# 03_-_SCHEMATIC.net
KiCad netlist of a schematic drawn in Altium Designer
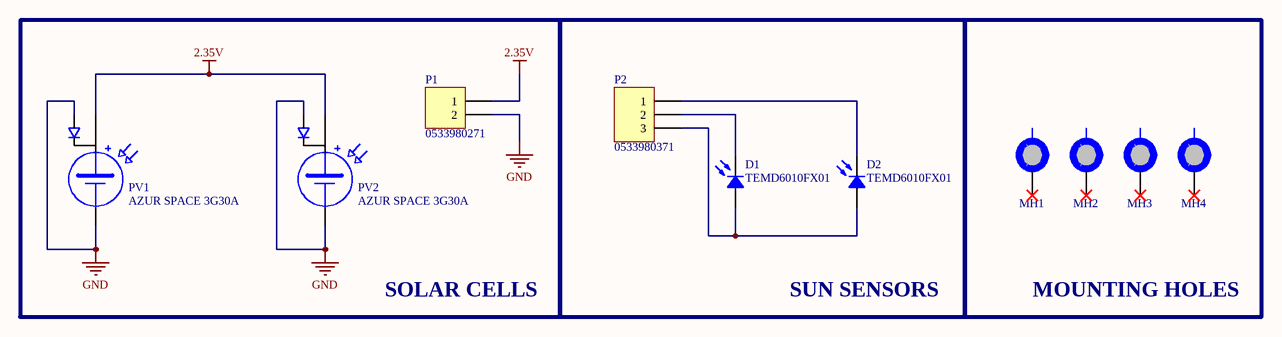
[diagram p0: [03] - SCHEMATIC.SchDoc]

(export (version "E")
  (design (tool "Eeschema 10.0.6"))
  (components
    (comp (ref "D1")
      (value "TEMD6010FX01")
      (footprint "TEMD6010FX01")
      (description "Ambient Light Sensor")
      (fields (field (name "MANUFACTURER") "Vishay Semiconductors"))
      (libsource (lib "UVG") (part "TEMD6010FX01"))
    )
    (comp (ref "D2")
      (value "TEMD6010FX01")
      (footprint "TEMD6010FX01")
      (description "Ambient Light Sensor")
      (fields (field (name "MANUFACTURER") "Vishay Semiconductors"))
      (libsource (lib "UVG") (part "TEMD6010FX01"))
    )
    (comp (ref "MH1")
      (value "MH_3.8MMNC_2.5MMD")
      (footprint "MH_3.8MMNC_2MMD_NON_COPPER_NPTH")
      (description "Mounting Hole 3.8mm Diameter (Non Copper), 2.5mm Drill NPTH")
      (libsource (lib "UVG") (part "MH_3.8MMNC_2MMD"))
    )
    (comp (ref "MH2")
      (value "MH_3.8MMNC_2.5MMD")
      (footprint "MH_3.8MMNC_2MMD_NON_COPPER_NPTH")
      (description "Mounting Hole 3.8mm Diameter (Non Copper), 2.5mm Drill NPTH")
      (libsource (lib "UVG") (part "MH_3.8MMNC_2MMD"))
    )
    (comp (ref "MH3")
      (value "MH_3.8MMNC_2.5MMD")
      (footprint "MH_3.8MMNC_2MMD_NON_COPPER_NPTH")
      (description "Mounting Hole 3.8mm Diameter (Non Copper), 2.5mm Drill NPTH")
      (libsource (lib "UVG") (part "MH_3.8MMNC_2MMD"))
    )
    (comp (ref "MH4")
      (value "MH_3.8MMNC_2.5MMD")
      (footprint "MH_3.8MMNC_2MMD_NON_COPPER_NPTH")
      (description "Mounting Hole 3.8mm Diameter (Non Copper), 2.5mm Drill NPTH")
      (libsource (lib "UVG") (part "MH_3.8MMNC_2MMD"))
    )
    (comp (ref "P1")
      (value "0533980271")
      (footprint "0533980271")
      (description "2 Positions Header, Shrouded Connector 0.049\" (1.25mm) Surface Mount, Right Angle Tin")
      (fields (field (name "MANUFACTURER") "Molex"))
      (libsource (lib "UVG") (part "0533980271"))
    )
    (comp (ref "P2")
      (value "0533980371")
      (footprint "0533980371")
      (description "3 Positions Header, Shrouded Connector 0.049\" (1.25mm) Surface Mount Tin")
      (fields (field (name "MANUFACTURER") "Molex"))
      (libsource (lib "UVG") (part "0533980371"))
    )
    (comp (ref "PV1")
      (value "AZUR SPACE 3G30A")
      (footprint "AZUR SPACE 3G30A")
      (description "30% Triple Junction GaAs Solar Cell Assembly")
      (libsource (lib "UVG") (part "AZUR SPACE 3G30A"))
    )
    (comp (ref "PV2")
      (value "AZUR SPACE 3G30A")
      (footprint "AZUR SPACE 3G30A")
      (description "30% Triple Junction GaAs Solar Cell Assembly")
      (libsource (lib "UVG") (part "AZUR SPACE 3G30A"))
    )
  )
  (nets
    (net (code "1") (name "2.35V") (class "Default")
      (node (ref "P1") (pin "1") (pinfunction "1_1") (pintype "passive"))
      (node (ref "PV1") (pin "1") (pinfunction "1_1") (pintype "passive"))
      (node (ref "PV2") (pin "1") (pinfunction "1_1") (pintype "passive"))
    )
    (net (code "2") (name "GND") (class "Default")
      (node (ref "P1") (pin "2") (pinfunction "2_2") (pintype "passive"))
      (node (ref "PV1") (pin "2") (pinfunction "2_2") (pintype "passive"))
      (node (ref "PV1") (pin "3") (pinfunction "3_3") (pintype "passive"))
      (node (ref "PV2") (pin "2") (pinfunction "2_2") (pintype "passive"))
      (node (ref "PV2") (pin "3") (pinfunction "3_3") (pintype "passive"))
    )
    (net (code "3") (name "Net-(D1-Pad1)") (class "Default")
      (node (ref "D1") (pin "1") (pinfunction "1_1") (pintype "passive"))
      (node (ref "D2") (pin "1") (pinfunction "1_1") (pintype "passive"))
      (node (ref "P2") (pin "3") (pinfunction "3_3") (pintype "passive"))
    )
    (net (code "4") (name "Net-(D1-Pad2)") (class "Default")
      (node (ref "D1") (pin "2") (pinfunction "2_2") (pintype "passive"))
      (node (ref "P2") (pin "2") (pinfunction "2_2") (pintype "passive"))
    )
    (net (code "5") (name "Net-(D2-Pad2)") (class "Default")
      (node (ref "D2") (pin "2") (pinfunction "2_2") (pintype "passive"))
      (node (ref "P2") (pin "1") (pinfunction "1_1") (pintype "passive"))
    )
    (net (code "6") (name "unconnected-(MH1-Pad1)") (class "Default")
      (node (ref "MH1") (pin "1") (pinfunction "1_1") (pintype "passive"))
    )
    (net (code "7") (name "unconnected-(MH2-Pad1)") (class "Default")
      (node (ref "MH2") (pin "1") (pinfunction "1_1") (pintype "passive"))
    )
    (net (code "8") (name "unconnected-(MH3-Pad1)") (class "Default")
      (node (ref "MH3") (pin "1") (pinfunction "1_1") (pintype "passive"))
    )
    (net (code "9") (name "unconnected-(MH4-Pad1)") (class "Default")
      (node (ref "MH4") (pin "1") (pinfunction "1_1") (pintype "passive"))
    )
  )
)
